# Top.net
KiCad netlist of a schematic drawn in Altium Designer
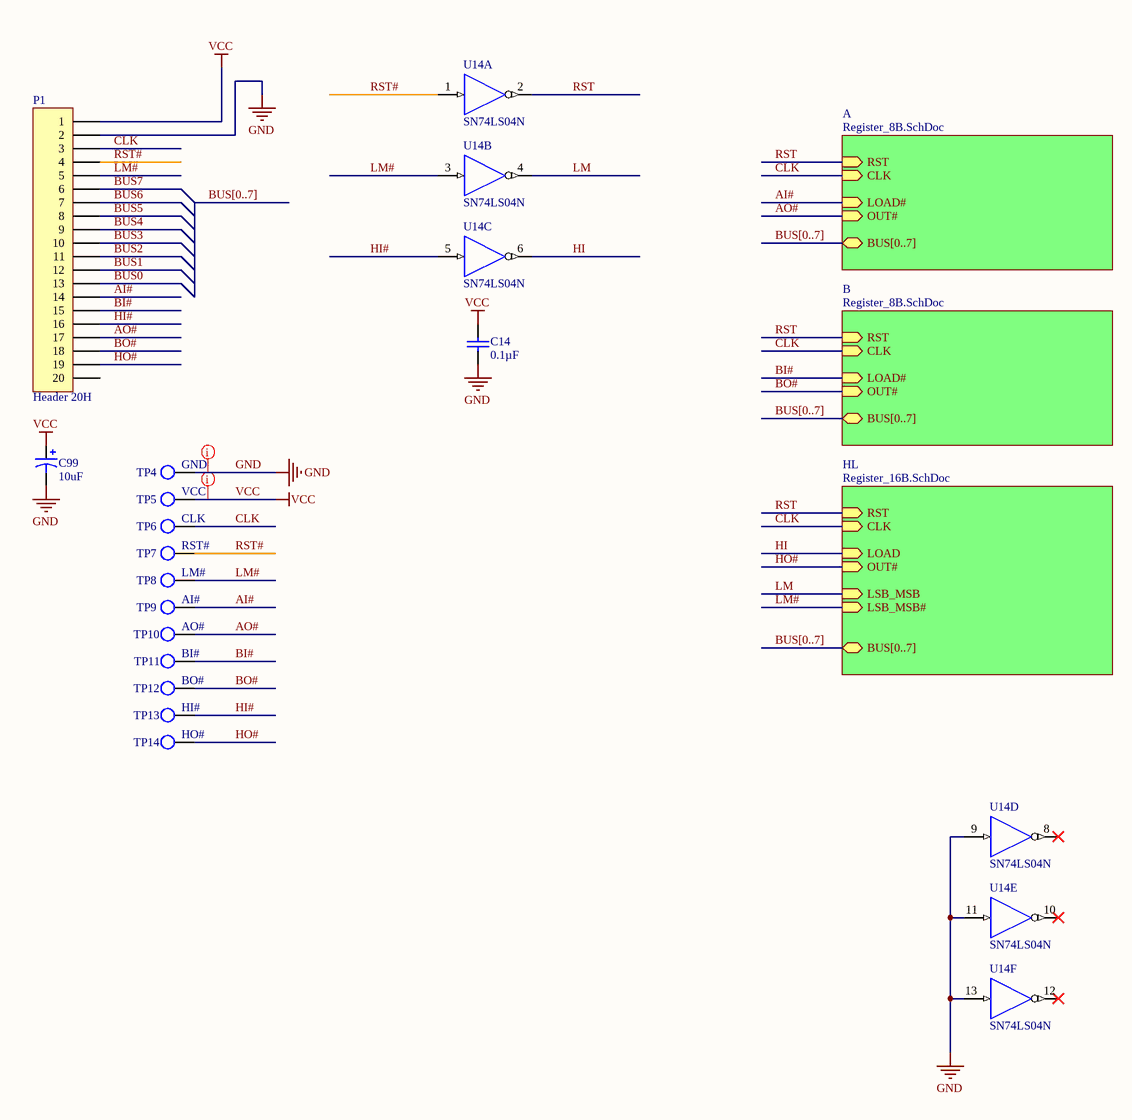
[diagram p0: Top.SchDoc]

(export (version "E")
  (design (tool "Eeschema 10.0.6"))
  (components
    (comp (ref "C14")
      (value "K104K15X7RF5TL2")
      (footprint "VISH-K104K15X7RF5TL2")
      (description "Ceramic Capacitor, 100 nF, +/- 10%, 50 V, -55 to 125 degC, 2-Pin THD, RoHS, Tape and Reel")
      (fields
        (field (name "MANUFACTURER") "Vishay")
        (field (name "TOLERANCE") "±10%")
        (field (name "CAPACITANCE") "0.1µF")
      )
      (libsource (lib "Altium Content Vault") (part "CAP-NP-2"))
    )
    (comp (ref "C99")
      (value "10uF")
      (footprint "C5x7")
      (description "Polarized Capacitor")
      (fields (field (name "Comment") "Cap Pol5") (field (name "PUBLISHER") "Altium Limited"))
      (libsource (lib "Miscellaneous Devices") (part "Cap Pol5"))
    )
    (comp (ref "P1")
      (value "Header 20H")
      (footprint "HDR1X20H")
      (description "Header, 20-Pin, Right Angle")
      (fields (field (name "PUBLISHER") "Altium Limited"))
      (libsource (lib "Miscellaneous Connectors") (part "Header 20H"))
    )
    (comp (ref "TP4") (value "GND") (footprint "KSTN-5011_V") (libsource (lib "TP") (part "TP")))
    (comp (ref "TP5") (value "VCC") (footprint "KSTN-5011_V") (libsource (lib "TP") (part "TP")))
    (comp (ref "TP6") (value "CLK") (footprint "KSTN-5011_V") (libsource (lib "TP") (part "TP")))
    (comp (ref "TP7") (value "RST#") (footprint "KSTN-5011_V") (libsource (lib "TP") (part "TP")))
    (comp (ref "TP8") (value "LM#") (footprint "KSTN-5011_V") (libsource (lib "TP") (part "TP")))
    (comp (ref "TP9") (value "AI#") (footprint "KSTN-5011_V") (libsource (lib "TP") (part "TP")))
    (comp (ref "TP10") (value "AO#") (footprint "KSTN-5011_V") (libsource (lib "TP") (part "TP")))
    (comp (ref "TP11") (value "BI#") (footprint "KSTN-5011_V") (libsource (lib "TP") (part "TP")))
    (comp (ref "TP12") (value "BO#") (footprint "KSTN-5011_V") (libsource (lib "TP") (part "TP")))
    (comp (ref "TP13") (value "HI#") (footprint "KSTN-5011_V") (libsource (lib "TP") (part "TP")))
    (comp (ref "TP14") (value "HO#") (footprint "KSTN-5011_V") (libsource (lib "TP") (part "TP")))
    (comp (ref "U14")
      (value "SN74LS04N")
      (footprint "N014")
      (description "Hex Inverter")
      (fields (field (name "PUBLISHER") "Altium Limited"))
      (libsource (lib "TI Logic Gate 2") (part "SN74LS04N"))
    )
  )
  (nets
    (net (code "1") (name "/AI#") (class "Default")
      (node (ref "P1") (pin "14") (pinfunction "14_14") (pintype "passive"))
      (node (ref "TP9") (pin "1") (pintype "passive"))
    )
    (net (code "2") (name "/AO#") (class "Default")
      (node (ref "P1") (pin "17") (pinfunction "17_17") (pintype "passive"))
      (node (ref "TP10") (pin "1") (pintype "passive"))
    )
    (net (code "3") (name "/BI#") (class "Default")
      (node (ref "P1") (pin "15") (pinfunction "15_15") (pintype "passive"))
      (node (ref "TP11") (pin "1") (pintype "passive"))
    )
    (net (code "4") (name "/BO#") (class "Default")
      (node (ref "P1") (pin "18") (pinfunction "18_18") (pintype "passive"))
      (node (ref "TP12") (pin "1") (pintype "passive"))
    )
    (net (code "5") (name "/BUS0") (class "Default")
      (node (ref "P1") (pin "13") (pinfunction "13_13") (pintype "passive"))
    )
    (net (code "6") (name "/BUS1") (class "Default")
      (node (ref "P1") (pin "12") (pinfunction "12_12") (pintype "passive"))
    )
    (net (code "7") (name "/BUS2") (class "Default")
      (node (ref "P1") (pin "11") (pinfunction "11_11") (pintype "passive"))
    )
    (net (code "8") (name "/BUS3") (class "Default")
      (node (ref "P1") (pin "10") (pinfunction "10_10") (pintype "passive"))
    )
    (net (code "9") (name "/BUS4") (class "Default")
      (node (ref "P1") (pin "9") (pinfunction "9_9") (pintype "passive"))
    )
    (net (code "10") (name "/BUS5") (class "Default")
      (node (ref "P1") (pin "8") (pinfunction "8_8") (pintype "passive"))
    )
    (net (code "11") (name "/BUS6") (class "Default")
      (node (ref "P1") (pin "7") (pinfunction "7_7") (pintype "passive"))
    )
    (net (code "12") (name "/BUS7") (class "Default")
      (node (ref "P1") (pin "6") (pinfunction "6_6") (pintype "passive"))
    )
    (net (code "14") (name "/CLK") (class "Default")
      (node (ref "P1") (pin "3") (pinfunction "3_3") (pintype "passive"))
      (node (ref "TP6") (pin "1") (pintype "passive"))
    )
    (net (code "15") (name "/HI") (class "Default")
      (node (ref "U14") (pin "6") (pinfunction "Y_6") (pintype "output"))
    )
    (net (code "16") (name "/HI#") (class "Default")
      (node (ref "P1") (pin "16") (pinfunction "16_16") (pintype "passive"))
      (node (ref "TP13") (pin "1") (pintype "passive"))
      (node (ref "U14") (pin "5") (pinfunction "A_5") (pintype "input"))
    )
    (net (code "17") (name "/HO#") (class "Default")
      (node (ref "P1") (pin "19") (pinfunction "19_19") (pintype "passive"))
      (node (ref "TP14") (pin "1") (pintype "passive"))
    )
    (net (code "18") (name "/LM") (class "Default")
      (node (ref "U14") (pin "4") (pinfunction "Y_4") (pintype "output"))
    )
    (net (code "19") (name "/LM#") (class "Default")
      (node (ref "P1") (pin "5") (pinfunction "5_5") (pintype "passive"))
      (node (ref "TP8") (pin "1") (pintype "passive"))
      (node (ref "U14") (pin "3") (pinfunction "A_3") (pintype "input"))
    )
    (net (code "20") (name "/RST") (class "Default")
      (node (ref "U14") (pin "2") (pinfunction "Y_2") (pintype "output"))
    )
    (net (code "21") (name "/RST#") (class "Default")
      (node (ref "P1") (pin "4") (pinfunction "4_4") (pintype "passive"))
      (node (ref "TP7") (pin "1") (pintype "passive"))
      (node (ref "U14") (pin "1") (pinfunction "A_1") (pintype "input"))
    )
    (net (code "22") (name "GND") (class "Default")
      (node (ref "C14") (pin "2") (pinfunction "2_2") (pintype "passive"))
      (node (ref "C99") (pin "2") (pinfunction "2_2") (pintype "passive"))
      (node (ref "P1") (pin "2") (pinfunction "2_2") (pintype "passive"))
      (node (ref "TP4") (pin "1") (pintype "passive"))
      (node (ref "U14") (pin "11") (pinfunction "A_11") (pintype "input"))
      (node (ref "U14") (pin "13") (pinfunction "A_13") (pintype "input"))
      (node (ref "U14") (pin "7") (pinfunction "GND_7") (pintype "power_in"))
      (node (ref "U14") (pin "9") (pinfunction "A_9") (pintype "input"))
    )
    (net (code "23") (name "VCC") (class "Default")
      (node (ref "C14") (pin "1") (pinfunction "1_1") (pintype "passive"))
      (node (ref "C99") (pin "1") (pinfunction "1_1") (pintype "passive"))
      (node (ref "P1") (pin "1") (pinfunction "1_1") (pintype "passive"))
      (node (ref "TP5") (pin "1") (pintype "passive"))
      (node (ref "U14") (pin "14") (pinfunction "VCC_14") (pintype "power_in"))
    )
    (net (code "24") (name "unconnected-(P1-Pad20)") (class "Default")
      (node (ref "P1") (pin "20") (pinfunction "20_20") (pintype "passive"))
    )
    (net (code "25") (name "unconnected-(U14D-Y-Pad8)") (class "Default")
      (node (ref "U14") (pin "8") (pinfunction "Y_8") (pintype "output+no_connect"))
    )
    (net (code "26") (name "unconnected-(U14E-Y-Pad10)") (class "Default")
      (node (ref "U14") (pin "10") (pinfunction "Y_10") (pintype "output+no_connect"))
    )
    (net (code "27") (name "unconnected-(U14F-Y-Pad12)") (class "Default")
      (node (ref "U14") (pin "12") (pinfunction "Y_12") (pintype "output+no_connect"))
    )
  )
)
